# FM-Super-Regen.net
KiCad netlist of a schematic drawn in EAGLE
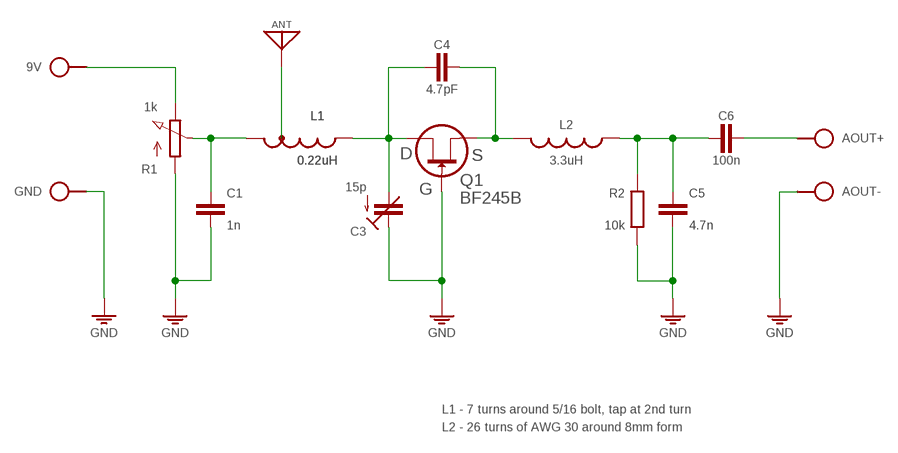
[diagram p0: schematic, sheet 1]

(export (version "E")
  (design (tool "Eeschema 10.0.6"))
  (components
    (comp (ref "9V")
      (value "SPAD")
      (footprint "eagle-import:SPAD")
      (libsource (lib "eagle-import") (part "SPAD"))
    )
    (comp (ref "ANT")
      (value "ANT")
      (footprint "eagle-import:SPAD")
      (libsource (lib "eagle-import") (part "ANT"))
    )
    (comp (ref "AOUT+")
      (value "SPAD")
      (footprint "eagle-import:SPAD")
      (libsource (lib "eagle-import") (part "SPAD"))
    )
    (comp (ref "AOUT-")
      (value "SPAD")
      (footprint "eagle-import:SPAD")
      (libsource (lib "eagle-import") (part "SPAD"))
    )
    (comp (ref "C1")
      (value "1n")
      (footprint "eagle-import:C050-020X036_V")
      (libsource (lib "eagle-import") (part "C050-020X036/V"))
    )
    (comp (ref "C3")
      (value "15p")
      (footprint "eagle-import:TRIM-2222-808")
      (libsource (lib "eagle-import") (part "C-TR-PH201272222-808-2PIN"))
    )
    (comp (ref "C4")
      (value "4.7pF")
      (footprint "eagle-import:C050-020X036")
      (libsource (lib "eagle-import") (part "C050-020X036"))
    )
    (comp (ref "C5")
      (value "4.7n")
      (footprint "eagle-import:C050-020X044")
      (libsource (lib "eagle-import") (part "C050-020X044"))
    )
    (comp (ref "C6")
      (value "100n")
      (footprint "eagle-import:C050-020X044")
      (libsource (lib "eagle-import") (part "C050-020X044"))
    )
    (comp (ref "GND")
      (value "SPAD")
      (footprint "eagle-import:SPAD")
      (libsource (lib "eagle-import") (part "SPAD"))
    )
    (comp (ref "L1")
      (value "0.22uH")
      (footprint "eagle-import:L-08_10-X-TAP1")
      (libsource (lib "eagle-import") (part "L-TAP1L-08/10-X-TAP1"))
    )
    (comp (ref "L2")
      (value "3.3uH")
      (footprint "eagle-import:L-BODY")
      (libsource (lib "eagle-import") (part "L-BODY"))
    )
    (comp (ref "Q1")
      (value "BF245B")
      (footprint "eagle-import:TO92")
      (libsource (lib "eagle-import") (part "BF245B"))
    )
    (comp (ref "R1")
      (value "1k")
      (footprint "eagle-import:POT-V")
      (libsource (lib "eagle-import") (part "POT-V"))
    )
    (comp (ref "R2")
      (value "10k")
      (footprint "eagle-import:0204_10")
      (libsource (lib "eagle-import") (part "R0204/10"))
    )
  )
  (nets
    (net (code "1") (name "GND") (class "Default")
      (node (ref "AOUT-") (pin "1") (pinfunction "P$1_1") (pintype "bidirectional"))
      (node (ref "C1") (pin "2") (pinfunction "2_2") (pintype "passive"))
      (node (ref "C3") (pin "1") (pinfunction "E_1") (pintype "passive"))
      (node (ref "C5") (pin "2") (pinfunction "2_2") (pintype "passive"))
      (node (ref "GND") (pin "1") (pinfunction "P$1_1") (pintype "bidirectional"))
      (node (ref "Q1") (pin "1") (pinfunction "G_1") (pintype "passive"))
      (node (ref "R1") (pin "A") (pinfunction "A_A") (pintype "passive"))
      (node (ref "R2") (pin "1") (pinfunction "1_1") (pintype "passive"))
    )
    (net (code "2") (name "Net-(9V-P$1)") (class "Default")
      (node (ref "9V") (pin "1") (pinfunction "P$1_1") (pintype "bidirectional"))
      (node (ref "R1") (pin "E") (pinfunction "E_E") (pintype "passive"))
    )
    (net (code "3") (name "Net-(AOUT+-P$1)") (class "Default")
      (node (ref "AOUT+") (pin "1") (pinfunction "P$1_1") (pintype "bidirectional"))
      (node (ref "C6") (pin "2") (pinfunction "2_2") (pintype "passive"))
    )
    (net (code "4") (name "Net-(C1-Pad1)") (class "Default")
      (node (ref "C1") (pin "1") (pinfunction "1_1") (pintype "passive"))
      (node (ref "L1") (pin "1") (pinfunction "1_1") (pintype "passive"))
      (node (ref "R1") (pin "S") (pinfunction "S_S") (pintype "passive"))
    )
    (net (code "5") (name "Net-(C3-A)") (class "Default")
      (node (ref "C3") (pin "2") (pinfunction "A_2") (pintype "passive"))
      (node (ref "C4") (pin "1") (pinfunction "1_1") (pintype "passive"))
      (node (ref "L1") (pin "2") (pinfunction "2_2") (pintype "passive"))
      (node (ref "Q1") (pin "3") (pinfunction "D_3") (pintype "passive"))
    )
    (net (code "6") (name "Net-(L1-T)") (class "Default")
      (node (ref "ANT") (pin "1") (pinfunction "1_1") (pintype "output"))
      (node (ref "L1") (pin "3") (pinfunction "T_3") (pintype "passive"))
    )
    (net (code "7") (name "Net-(L2-1)") (class "Default")
      (node (ref "C5") (pin "1") (pinfunction "1_1") (pintype "passive"))
      (node (ref "C6") (pin "1") (pinfunction "1_1") (pintype "passive"))
      (node (ref "L2") (pin "2") (pinfunction "1_2") (pintype "passive"))
      (node (ref "R2") (pin "2") (pinfunction "2_2") (pintype "passive"))
    )
    (net (code "8") (name "Net-(L2-2)") (class "Default")
      (node (ref "C4") (pin "2") (pinfunction "2_2") (pintype "passive"))
      (node (ref "L2") (pin "3") (pinfunction "2_3") (pintype "passive"))
      (node (ref "Q1") (pin "2") (pinfunction "S_2") (pintype "passive"))
    )
  )
)
